# 05_Ethernet.net
KiCad netlist of a schematic drawn in Altium Designer
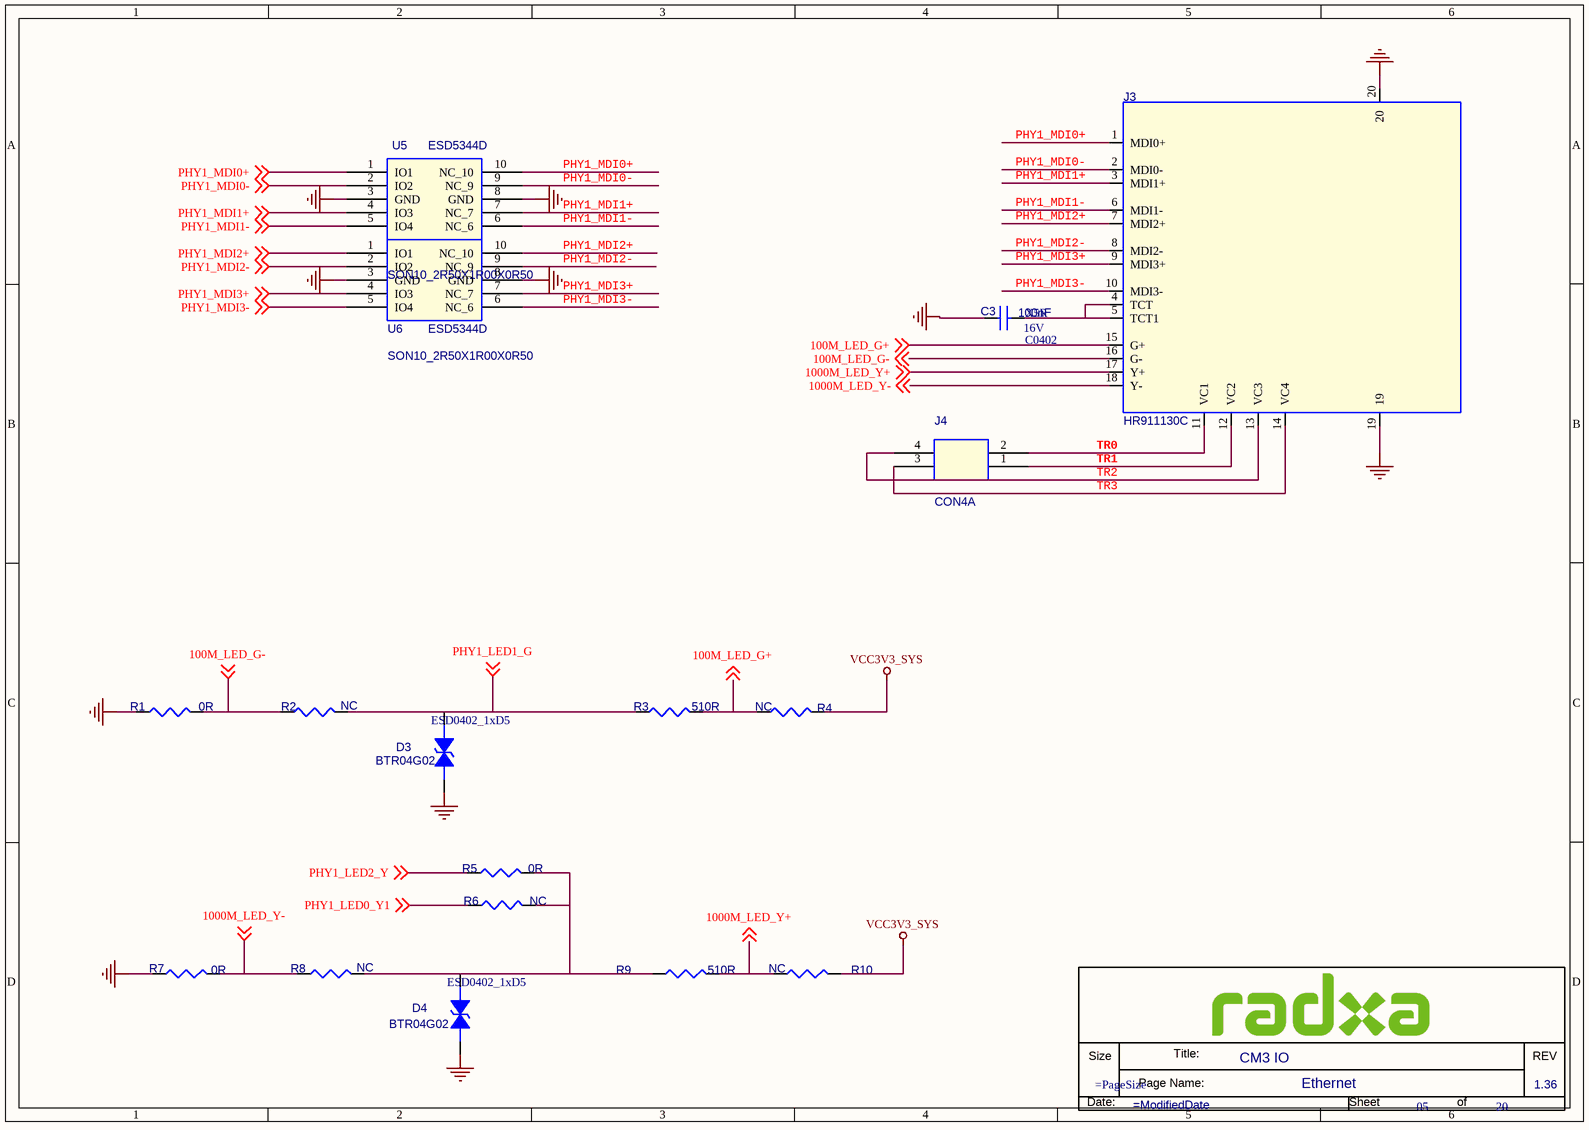
[diagram p0: 05.Ethernet.SchDoc]

(export (version "E")
  (design (tool "Eeschema 10.0.6"))
  (components
    (comp (ref "C3")
      (value "100nF")
      (footprint "C0402")
      (description "cap,100.00nF,+/-10%,16V,X5R,C0402")
      (fields
        (field (name "VOLTAGE") "16V")
        (field (name "PCB FOOTPRINT") "C0402")
        (field (name "DIELECTRIC") "X5R")
        (field (name "MANUFACTURER") "TDK")
        (field (name "TOLERANCE") "10%")
        (field (name "CREATED BY") "JJJ")
      )
      (libsource (lib "*") (part "CAP NP_0"))
    )
    (comp (ref "D3")
      (value "BTR04G02")
      (footprint "ESD0402_1xD5")
      (description "1-Line, Bi-directional, Transient Voltage Suppressors.17.5pF.")
      (fields
        (field (name "PCB FOOTPRINT") "ESD0402_1xD5")
        (field (name "MANUFACTURER") "WillSemi(韦尔半导体)")
        (field (name "CREATED BY") "JJJ")
      )
      (libsource (lib "*") (part "DIODE BI_DIR TRIG_0"))
    )
    (comp (ref "D4")
      (value "BTR04G02")
      (footprint "ESD0402_1xD5")
      (description "1-Line, Bi-directional, Transient Voltage Suppressors.17.5pF.")
      (fields
        (field (name "PCB FOOTPRINT") "ESD0402_1xD5")
        (field (name "MANUFACTURER") "WillSemi(韦尔半导体)")
        (field (name "CREATED BY") "JJJ")
      )
      (libsource (lib "*") (part "DIODE BI_DIR TRIG_0"))
    )
    (comp (ref "J3")
      (value "HR911130C")
      (footprint "RJ45_PULSE")
      (description "千兆网口接口，内置变压器")
      (fields (field (name "CREATED BY") "JJJ"))
      (libsource (lib "*") (part "HR911130C_1"))
    )
    (comp (ref "J4") (value "CON4A") (footprint "DIP4PIN-2_54MM-2X2") (libsource (lib "*") (part "CON4A_0")))
    (comp (ref "R1")
      (value "0R")
      (footprint "R0402")
      (description "通用厚膜电阻,0R,+/-5%,R0402,1/16W.")
      (fields
        (field (name "TOLERANCE") "5%")
        (field (name "MANUFACTURER") "YAGEO")
        (field (name "CREATED BY") "YTL")
      )
      (libsource (lib "*") (part "RESISTOR_0"))
    )
    (comp (ref "R2")
      (value "NC")
      (footprint "R0402")
      (description "通用厚膜电阻,0R,+/-5%,R0402,1/16W.")
      (fields
        (field (name "MANUFACTURER") "YAGEO")
        (field (name "TOLERANCE") "5%")
        (field (name "CREATED BY") "YTL")
      )
      (libsource (lib "*") (part "RESISTOR_0"))
    )
    (comp (ref "R3")
      (value "510R")
      (footprint "R0402")
      (description "通用厚膜电阻,0R,+/-5%,R0402,1/16W.")
      (fields
        (field (name "TOLERANCE") "5%")
        (field (name "MANUFACTURER") "YAGEO")
        (field (name "CREATED BY") "YTL")
      )
      (libsource (lib "*") (part "RESISTOR_0"))
    )
    (comp (ref "R4")
      (value "NC")
      (footprint "R0402")
      (description "通用厚膜电阻,510R,+/-5%,R0402,1/16W.")
      (fields
        (field (name "MANUFACTURER") "YAGEO")
        (field (name "TOLERANCE") "5%")
        (field (name "CREATED BY") "YTL")
      )
      (libsource (lib "*") (part "RESISTOR_0"))
    )
    (comp (ref "R5")
      (value "0R")
      (footprint "R0402")
      (description "通用厚膜电阻,0R,+/-5%,R0402,1/16W.")
      (fields
        (field (name "MANUFACTURER") "YAGEO")
        (field (name "TOLERANCE") "5%")
        (field (name "CREATED BY") "YTL")
      )
      (libsource (lib "*") (part "RESISTOR_0"))
    )
    (comp (ref "R6")
      (value "NC")
      (footprint "R0402")
      (description "通用厚膜电阻,0R,+/-5%,R0402,1/16W.")
      (fields
        (field (name "MANUFACTURER") "YAGEO")
        (field (name "TOLERANCE") "5%")
        (field (name "CREATED BY") "YTL")
      )
      (libsource (lib "*") (part "RESISTOR_0"))
    )
    (comp (ref "R7")
      (value "0R")
      (footprint "R0402")
      (description "通用厚膜电阻,0R,+/-5%,R0402,1/16W.")
      (fields
        (field (name "MANUFACTURER") "YAGEO")
        (field (name "TOLERANCE") "5%")
        (field (name "CREATED BY") "YTL")
      )
      (libsource (lib "*") (part "RESISTOR_0"))
    )
    (comp (ref "R8")
      (value "NC")
      (footprint "R0402")
      (description "通用厚膜电阻,0R,+/-5%,R0402,1/16W.")
      (fields
        (field (name "MANUFACTURER") "YAGEO")
        (field (name "TOLERANCE") "5%")
        (field (name "CREATED BY") "YTL")
      )
      (libsource (lib "*") (part "RESISTOR_0"))
    )
    (comp (ref "R9")
      (value "510R")
      (footprint "R0402")
      (description "通用厚膜电阻,0R,+/-5%,R0402,1/16W.")
      (fields
        (field (name "MANUFACTURER") "YAGEO")
        (field (name "TOLERANCE") "5%")
        (field (name "CREATED BY") "YTL")
      )
      (libsource (lib "*") (part "RESISTOR_0"))
    )
    (comp (ref "R10")
      (value "NC")
      (footprint "R0402")
      (description "通用厚膜电阻,510R,+/-5%,R0402,1/16W.")
      (fields
        (field (name "TOLERANCE") "5%")
        (field (name "MANUFACTURER") "YAGEO")
        (field (name "CREATED BY") "YTL")
      )
      (libsource (lib "*") (part "RESISTOR_0"))
    )
    (comp (ref "U5")
      (value "ESD5344D")
      (footprint "SON10_2R50X1R00X0R50")
      (description "4-Lines, Uni-directional, Ultra-low Capacitance Transient Voltage Suppressors")
      (fields
        (field (name "PCB FOOTPRINT") "SON10_2R50X1R00X0R50")
        (field (name "MANUFACTURER") "WillSemi(韦尔半导体)")
        (field (name "CREATED BY") "JJJ")
      )
      (libsource (lib "*") (part "ESD_ESD5304D"))
    )
    (comp (ref "U6")
      (value "ESD5344D")
      (footprint "SON10_2R50X1R00X0R50")
      (description "4-Lines, Uni-directional, Ultra-low Capacitance Transient Voltage Suppressors")
      (fields
        (field (name "PCB FOOTPRINT") "SON10_2R50X1R00X0R50")
        (field (name "MANUFACTURER") "WillSemi(韦尔半导体)")
        (field (name "CREATED BY") "JJJ")
      )
      (libsource (lib "*") (part "ESD_ESD5304D"))
    )
  )
  (nets
    (net (code "1") (name "/TR0") (class "Default")
      (node (ref "J3") (pin "11") (pinfunction "VC1_11") (pintype "passive"))
      (node (ref "J4") (pin "2") (pinfunction "2_2") (pintype "passive"))
    )
    (net (code "2") (name "/TR1") (class "Default")
      (node (ref "J3") (pin "12") (pinfunction "VC2_12") (pintype "passive"))
      (node (ref "J4") (pin "1") (pinfunction "1_1") (pintype "passive"))
    )
    (net (code "3") (name "/TR2") (class "Default")
      (node (ref "J3") (pin "13") (pinfunction "VC3_13") (pintype "passive"))
      (node (ref "J4") (pin "4") (pinfunction "4_4") (pintype "passive"))
    )
    (net (code "4") (name "/TR3") (class "Default")
      (node (ref "J3") (pin "14") (pinfunction "VC4_14") (pintype "passive"))
      (node (ref "J4") (pin "3") (pinfunction "3_3") (pintype "passive"))
    )
    (net (code "5") (name "100M_LED_G+") (class "Default")
      (node (ref "J3") (pin "15") (pinfunction "G+_15") (pintype "passive"))
      (node (ref "R3") (pin "2") (pinfunction "2_2") (pintype "passive"))
      (node (ref "R4") (pin "1") (pinfunction "1_1") (pintype "passive"))
    )
    (net (code "6") (name "100M_LED_G-") (class "Default")
      (node (ref "J3") (pin "16") (pinfunction "G-_16") (pintype "passive"))
      (node (ref "R1") (pin "2") (pinfunction "2_2") (pintype "passive"))
      (node (ref "R2") (pin "1") (pinfunction "1_1") (pintype "passive"))
    )
    (net (code "7") (name "1000M_LED_Y+") (class "Default")
      (node (ref "J3") (pin "17") (pinfunction "Y+_17") (pintype "passive"))
      (node (ref "R10") (pin "1") (pinfunction "1_1") (pintype "passive"))
      (node (ref "R9") (pin "2") (pinfunction "2_2") (pintype "passive"))
    )
    (net (code "8") (name "1000M_LED_Y-") (class "Default")
      (node (ref "J3") (pin "18") (pinfunction "Y-_18") (pintype "passive"))
      (node (ref "R7") (pin "2") (pinfunction "2_2") (pintype "passive"))
      (node (ref "R8") (pin "1") (pinfunction "1_1") (pintype "passive"))
    )
    (net (code "9") (name "GND") (class "Default")
      (node (ref "C3") (pin "1") (pinfunction "1_1") (pintype "passive"))
      (node (ref "D3") (pin "1") (pinfunction "1_1") (pintype "passive"))
      (node (ref "D4") (pin "1") (pinfunction "1_1") (pintype "passive"))
      (node (ref "J3") (pin "19") (pinfunction "19_19") (pintype "passive"))
      (node (ref "J3") (pin "20") (pinfunction "20_20") (pintype "passive"))
      (node (ref "R1") (pin "1") (pinfunction "1_1") (pintype "passive"))
      (node (ref "R7") (pin "1") (pinfunction "1_1") (pintype "passive"))
      (node (ref "U5") (pin "3") (pinfunction "GND_3") (pintype "power_in"))
      (node (ref "U5") (pin "8") (pinfunction "GND_8") (pintype "power_in"))
      (node (ref "U6") (pin "3") (pinfunction "GND_3") (pintype "power_in"))
      (node (ref "U6") (pin "8") (pinfunction "GND_8") (pintype "power_in"))
    )
    (net (code "10") (name "Net-(D4-Pad2)") (class "Default")
      (node (ref "D4") (pin "2") (pinfunction "2_2") (pintype "passive"))
      (node (ref "R5") (pin "2") (pinfunction "2_2") (pintype "passive"))
      (node (ref "R6") (pin "2") (pinfunction "2_2") (pintype "passive"))
      (node (ref "R8") (pin "2") (pinfunction "2_2") (pintype "passive"))
      (node (ref "R9") (pin "1") (pinfunction "1_1") (pintype "passive"))
    )
    (net (code "11") (name "Net-(J3-TCT)") (class "Default")
      (node (ref "C3") (pin "2") (pinfunction "2_2") (pintype "passive"))
      (node (ref "J3") (pin "4") (pinfunction "TCT_4") (pintype "passive"))
      (node (ref "J3") (pin "5") (pinfunction "TCT1_5") (pintype "passive"))
    )
    (net (code "12") (name "PHY1_LED0_Y1") (class "Default")
      (node (ref "R6") (pin "1") (pinfunction "1_1") (pintype "passive"))
    )
    (net (code "13") (name "PHY1_LED1_G") (class "Default")
      (node (ref "D3") (pin "2") (pinfunction "2_2") (pintype "passive"))
      (node (ref "R2") (pin "2") (pinfunction "2_2") (pintype "passive"))
      (node (ref "R3") (pin "1") (pinfunction "1_1") (pintype "passive"))
    )
    (net (code "14") (name "PHY1_LED2_Y") (class "Default")
      (node (ref "R5") (pin "1") (pinfunction "1_1") (pintype "passive"))
    )
    (net (code "15") (name "PHY1_MDI0+") (class "Default")
      (node (ref "J3") (pin "1") (pinfunction "MDI0+_1") (pintype "passive"))
      (node (ref "U5") (pin "1") (pinfunction "IO1_1") (pintype "passive"))
      (node (ref "U5") (pin "10") (pinfunction "NC_10_10") (pintype "passive"))
    )
    (net (code "16") (name "PHY1_MDI0-") (class "Default")
      (node (ref "J3") (pin "2") (pinfunction "MDI0-_2") (pintype "passive"))
      (node (ref "U5") (pin "2") (pinfunction "IO2_2") (pintype "passive"))
      (node (ref "U5") (pin "9") (pinfunction "NC_9_9") (pintype "passive"))
    )
    (net (code "17") (name "PHY1_MDI1+") (class "Default")
      (node (ref "J3") (pin "3") (pinfunction "MDI1+_3") (pintype "passive"))
      (node (ref "U5") (pin "4") (pinfunction "IO3_4") (pintype "passive"))
      (node (ref "U5") (pin "7") (pinfunction "NC_7_7") (pintype "passive"))
    )
    (net (code "18") (name "PHY1_MDI1-") (class "Default")
      (node (ref "J3") (pin "6") (pinfunction "MDI1-_6") (pintype "passive"))
      (node (ref "U5") (pin "5") (pinfunction "IO4_5") (pintype "passive"))
      (node (ref "U5") (pin "6") (pinfunction "NC_6_6") (pintype "passive"))
    )
    (net (code "19") (name "PHY1_MDI2+") (class "Default")
      (node (ref "J3") (pin "7") (pinfunction "MDI2+_7") (pintype "passive"))
      (node (ref "U6") (pin "1") (pinfunction "IO1_1") (pintype "passive"))
      (node (ref "U6") (pin "10") (pinfunction "NC_10_10") (pintype "passive"))
    )
    (net (code "20") (name "PHY1_MDI2-") (class "Default")
      (node (ref "J3") (pin "8") (pinfunction "MDI2-_8") (pintype "passive"))
      (node (ref "U6") (pin "2") (pinfunction "IO2_2") (pintype "passive"))
      (node (ref "U6") (pin "9") (pinfunction "NC_9_9") (pintype "passive"))
    )
    (net (code "21") (name "PHY1_MDI3+") (class "Default")
      (node (ref "J3") (pin "9") (pinfunction "MDI3+_9") (pintype "passive"))
      (node (ref "U6") (pin "4") (pinfunction "IO3_4") (pintype "passive"))
      (node (ref "U6") (pin "7") (pinfunction "NC_7_7") (pintype "passive"))
    )
    (net (code "22") (name "PHY1_MDI3-") (class "Default")
      (node (ref "J3") (pin "10") (pinfunction "MDI3-_10") (pintype "passive"))
      (node (ref "U6") (pin "5") (pinfunction "IO4_5") (pintype "passive"))
      (node (ref "U6") (pin "6") (pinfunction "NC_6_6") (pintype "passive"))
    )
    (net (code "23") (name "VCC3V3_SYS") (class "Default")
      (node (ref "R10") (pin "2") (pinfunction "2_2") (pintype "passive"))
      (node (ref "R4") (pin "2") (pinfunction "2_2") (pintype "passive"))
    )
  )
)
